# encoder_tle_tiny.net
KiCad netlist of a schematic drawn in EAGLE
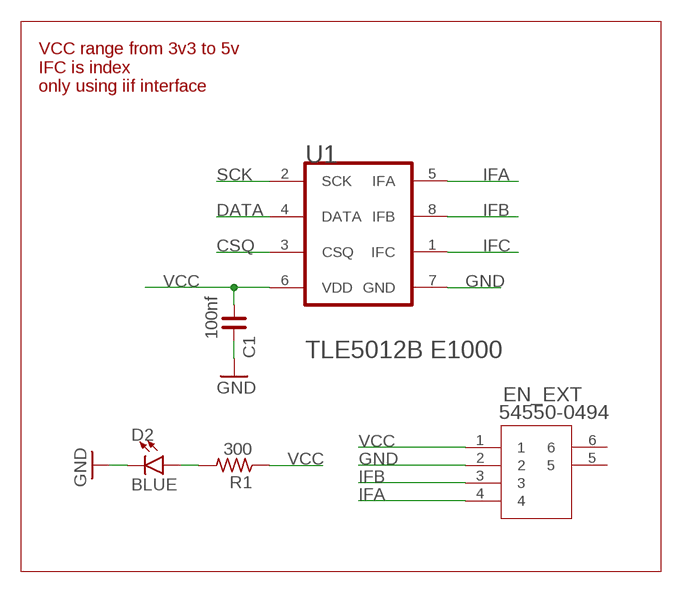
[diagram p0: schematic, sheet 1]

(export (version "E")
  (design (tool "Eeschema 10.0.6"))
  (components
    (comp (ref "C1")
      (value "100nf")
      (footprint "eagle-import:C0603")
      (libsource (lib "eagle-import") (part "C_0603"))
    )
    (comp (ref "D2")
      (value "BLUE")
      (footprint "eagle-import:LED-0603")
      (libsource (lib "eagle-import") (part "LED-BLUE0603"))
    )
    (comp (ref "EN_EXT")
      (value "54550-0494")
      (footprint "eagle-import:CON4_1X4_DRB2_MOL")
      (libsource (lib "eagle-import") (part "54550-0494"))
    )
    (comp (ref "R1")
      (value "300")
      (footprint "eagle-import:R0603")
      (libsource (lib "eagle-import") (part "R_0603"))
    )
    (comp (ref "U1")
      (value "INFINEON_TLE5012B_E1000INFINEON_TLE5012B_E1000_0_1")
      (footprint "eagle-import:INFINEON_TLE5012B_E1000_1")
      (fields (field (name "MF") "Infineon") (field (name "MPN") "TLE5012B E1000"))
      (libsource (lib "eagle-import") (part "INFINEON_TLE5012B_E1000INFINEON_TLE5012B_E1000_0_1"))
    )
  )
  (nets
    (net (code "1") (name "/CSQ") (class "Default")
      (node (ref "U1") (pin "3") (pinfunction "CSQ_3") (pintype "input"))
    )
    (net (code "2") (name "/DATA") (class "Default")
      (node (ref "U1") (pin "4") (pinfunction "DATA_4") (pintype "bidirectional"))
    )
    (net (code "3") (name "/IFA") (class "Default")
      (node (ref "EN_EXT") (pin "4") (pinfunction "4_4") (pintype "passive"))
      (node (ref "U1") (pin "5") (pinfunction "IFA_5") (pintype "open_collector"))
    )
    (net (code "4") (name "/IFB") (class "Default")
      (node (ref "EN_EXT") (pin "3") (pinfunction "3_3") (pintype "passive"))
      (node (ref "U1") (pin "8") (pinfunction "IFB_8") (pintype "open_collector"))
    )
    (net (code "5") (name "/IFC") (class "Default")
      (node (ref "U1") (pin "1") (pinfunction "IFC_1") (pintype "bidirectional"))
    )
    (net (code "6") (name "/SCK") (class "Default")
      (node (ref "U1") (pin "2") (pinfunction "SCK_2") (pintype "input"))
    )
    (net (code "7") (name "/VCC") (class "Default")
      (node (ref "C1") (pin "1") (pinfunction "1_1") (pintype "passive"))
      (node (ref "EN_EXT") (pin "1") (pinfunction "1_1") (pintype "passive"))
      (node (ref "R1") (pin "1") (pinfunction "1_1") (pintype "passive"))
      (node (ref "U1") (pin "6") (pinfunction "VDD_6") (pintype "power_in"))
    )
    (net (code "8") (name "GND") (class "Default")
      (node (ref "C1") (pin "2") (pinfunction "2_2") (pintype "passive"))
      (node (ref "D2") (pin "C") (pinfunction "C_C") (pintype "passive"))
      (node (ref "EN_EXT") (pin "2") (pinfunction "2_2") (pintype "passive"))
      (node (ref "U1") (pin "7") (pinfunction "GND_7") (pintype "power_in"))
    )
    (net (code "9") (name "Net-(D2-PadA)") (class "Default")
      (node (ref "D2") (pin "A") (pinfunction "A_A") (pintype "passive"))
      (node (ref "R1") (pin "2") (pinfunction "2_2") (pintype "passive"))
    )
    (net (code "10") (name "unconnected-(EN_EXT-Pad5)") (class "Default")
      (node (ref "EN_EXT") (pin "5") (pinfunction "5_5") (pintype "passive"))
    )
    (net (code "11") (name "unconnected-(EN_EXT-Pad6)") (class "Default")
      (node (ref "EN_EXT") (pin "6") (pinfunction "6_6") (pintype "passive"))
    )
  )
)
